# attinier85-motherboard-smd-mk-1_0.net
KiCad netlist of a schematic drawn in EAGLE
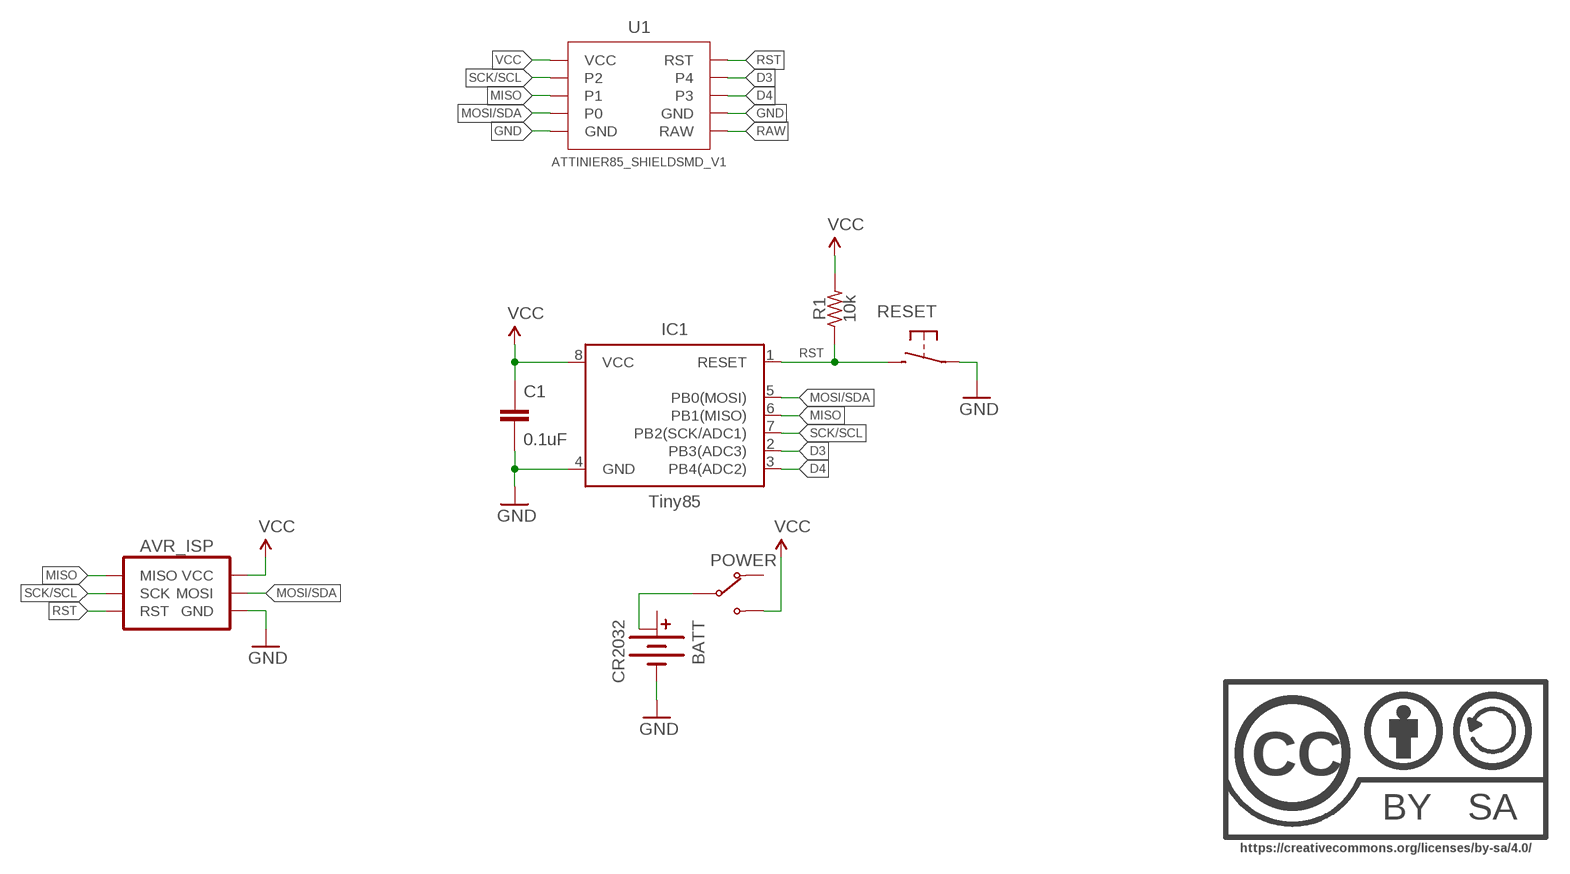
[diagram p0: schematic, sheet 1]

(export (version "E")
  (design (tool "Eeschema 10.0.6"))
  (components
    (comp (ref "AVR_ISP")
      (value "AVR_SPI_PRG_62X3_SMD")
      (footprint "eagle-import:2X3_SMD")
      (libsource (lib "eagle-import") (part "AVR_SPI_PRG_62X3_SMD"))
    )
    (comp (ref "BATT")
      (value "CR2032")
      (footprint "eagle-import:BATTCON_20MM_MINE")
      (libsource (lib "eagle-import") (part "BATTERY-COINCR2032_SMD"))
    )
    (comp (ref "C1")
      (value "0.1uF")
      (footprint "eagle-import:C0805")
      (libsource (lib "eagle-import") (part "CAPACITOR-CERAMICC0805"))
    )
    (comp (ref "IC1")
      (value "Tiny85")
      (footprint "eagle-import:SO08-EIAJ")
      (libsource (lib "eagle-import") (part "ATTINY45TINY85-20-SOICW"))
    )
    (comp (ref "POWER")
      (value "SWITCH-SPDTPTH-RA-2.54MM")
      (footprint "eagle-import:SPDT-RA-2.54MM")
      (libsource (lib "eagle-import") (part "SWITCH-SPDTPTH-RA-2.54MM"))
    )
    (comp (ref "R1")
      (value "10k")
      (footprint "eagle-import:R0805")
      (libsource (lib "eagle-import") (part "RESISTORR0805"))
    )
    (comp (ref "RESET")
      (value "DTS-6MM")
      (footprint "eagle-import:TACTILE-PTH-SIDE")
      (libsource (lib "eagle-import") (part "SPST-NO-TACT3MM-RA"))
    )
    (comp (ref "U$1")
      (value "CC-BY-SA-4.0NO-URL")
      (footprint "eagle-import:CC-BY-SA-4.0-NO-URL")
      (libsource (lib "eagle-import") (part "CC-BY-SA-4.0NO-URL"))
    )
    (comp (ref "U1")
      (value "ATTINIER85_SHIELDSMD_V1")
      (footprint "eagle-import:ATTINIER85_SHIELD_SMD")
      (libsource (lib "eagle-import") (part "ATTINIER85_SHIELDSMD_V1"))
    )
  )
  (nets
    (net (code "1") (name "D3") (class "Default")
      (node (ref "IC1") (pin "2") (pinfunction "PB3(ADC3)_2") (pintype "bidirectional"))
      (node (ref "U1") (pin "4") (pinfunction "P4_4") (pintype "bidirectional"))
    )
    (net (code "2") (name "D4") (class "Default")
      (node (ref "IC1") (pin "3") (pinfunction "PB4(ADC2)_3") (pintype "bidirectional"))
      (node (ref "U1") (pin "3") (pinfunction "P3_3") (pintype "bidirectional"))
    )
    (net (code "3") (name "GND") (class "Default")
      (node (ref "AVR_ISP") (pin "6") (pinfunction "GND_6") (pintype "passive"))
      (node (ref "BATT") (pin "BOTTOM") (pinfunction "-_BOTTOM") (pintype "bidirectional"))
      (node (ref "C1") (pin "2") (pinfunction "2_2") (pintype "passive"))
      (node (ref "IC1") (pin "4") (pinfunction "GND_4") (pintype "bidirectional"))
      (node (ref "RESET") (pin "1") (pinfunction "1_1") (pintype "passive"))
      (node (ref "U1") (pin "GND@1") (pinfunction "GND_GND@1") (pintype "bidirectional"))
      (node (ref "U1") (pin "GND@2") (pinfunction "GND_GND@2") (pintype "bidirectional"))
    )
    (net (code "4") (name "MISO") (class "Default")
      (node (ref "AVR_ISP") (pin "1") (pinfunction "MISO_1") (pintype "passive"))
      (node (ref "IC1") (pin "6") (pinfunction "PB1(MISO)_6") (pintype "bidirectional"))
      (node (ref "U1") (pin "1") (pinfunction "P1_1") (pintype "bidirectional"))
    )
    (net (code "5") (name "MOSI{slash}SDA") (class "Default")
      (node (ref "AVR_ISP") (pin "4") (pinfunction "MOSI_4") (pintype "passive"))
      (node (ref "IC1") (pin "5") (pinfunction "PB0(MOSI)_5") (pintype "bidirectional"))
      (node (ref "U1") (pin "0") (pinfunction "P0_0") (pintype "bidirectional"))
    )
    (net (code "6") (name "Net-(BATT-+1)") (class "Default")
      (node (ref "BATT") (pin "TOP@2") (pinfunction "+1_TOP@2") (pintype "bidirectional"))
      (node (ref "POWER") (pin "2") (pinfunction "COM_2") (pintype "passive"))
    )
    (net (code "7") (name "RAW") (class "Default")
      (node (ref "U1") (pin "RAW") (pinfunction "RAW_RAW") (pintype "bidirectional"))
    )
    (net (code "8") (name "RST") (class "Default")
      (node (ref "AVR_ISP") (pin "5") (pinfunction "RST_5") (pintype "passive"))
      (node (ref "IC1") (pin "1") (pinfunction "RESET_1") (pintype "bidirectional"))
      (node (ref "R1") (pin "1") (pinfunction "1_1") (pintype "passive"))
      (node (ref "RESET") (pin "2") (pinfunction "2_2") (pintype "passive"))
      (node (ref "U1") (pin "RST") (pinfunction "RST_RST") (pintype "bidirectional"))
    )
    (net (code "9") (name "SCK{slash}SCL") (class "Default")
      (node (ref "AVR_ISP") (pin "3") (pinfunction "SCK_3") (pintype "passive"))
      (node (ref "IC1") (pin "7") (pinfunction "PB2(SCK/ADC1)_7") (pintype "bidirectional"))
      (node (ref "U1") (pin "2") (pinfunction "P2_2") (pintype "bidirectional"))
    )
    (net (code "10") (name "VCC") (class "Default")
      (node (ref "AVR_ISP") (pin "2") (pinfunction "VCC_2") (pintype "passive"))
      (node (ref "C1") (pin "1") (pinfunction "1_1") (pintype "passive"))
      (node (ref "IC1") (pin "8") (pinfunction "VCC_8") (pintype "bidirectional"))
      (node (ref "POWER") (pin "3") (pinfunction "NO_3") (pintype "passive"))
      (node (ref "R1") (pin "2") (pinfunction "2_2") (pintype "passive"))
      (node (ref "U1") (pin "VCC") (pinfunction "VCC_VCC") (pintype "bidirectional"))
    )
    (net (code "11") (name "unconnected-(BATT-+-PadTOP@1)") (class "Default")
      (node (ref "BATT") (pin "TOP@1") (pinfunction "+_TOP@1") (pintype "bidirectional"))
    )
    (net (code "12") (name "unconnected-(POWER-NC-Pad1)") (class "Default")
      (node (ref "POWER") (pin "1") (pinfunction "NC_1") (pintype "passive"))
    )
  )
)
